# Conductivity_probe.net
KiCad netlist of a schematic drawn in EAGLE
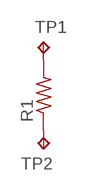
[diagram p0: schematic, sheet 1]

(export (version "E")
  (design (tool "Eeschema 10.0.6"))
  (components
    (comp (ref "R1")
      (value "R-US_0204/7")
      (footprint "eagle-import:0204_7")
      (libsource (lib "eagle-import") (part "R-US_0204/7"))
    )
    (comp (ref "TP1")
      (value "TPPAD1-17")
      (footprint "eagle-import:P1-17")
      (libsource (lib "eagle-import") (part "TPPAD1-17"))
    )
    (comp (ref "TP2")
      (value "TPPAD1-17")
      (footprint "eagle-import:P1-17")
      (libsource (lib "eagle-import") (part "TPPAD1-17"))
    )
  )
  (nets
    (net (code "1") (name "Net-(R1-Pad1)") (class "Default")
      (node (ref "R1") (pin "1") (pinfunction "1_1") (pintype "passive"))
      (node (ref "TP2") (pin "TP") (pinfunction "TP_TP") (pintype "input"))
    )
    (net (code "2") (name "Net-(R1-Pad2)") (class "Default")
      (node (ref "R1") (pin "2") (pinfunction "2_2") (pintype "passive"))
      (node (ref "TP1") (pin "TP") (pinfunction "TP_TP") (pintype "input"))
    )
  )
)
